# BrewPi_Shield.net
KiCad netlist of a schematic drawn in EAGLE
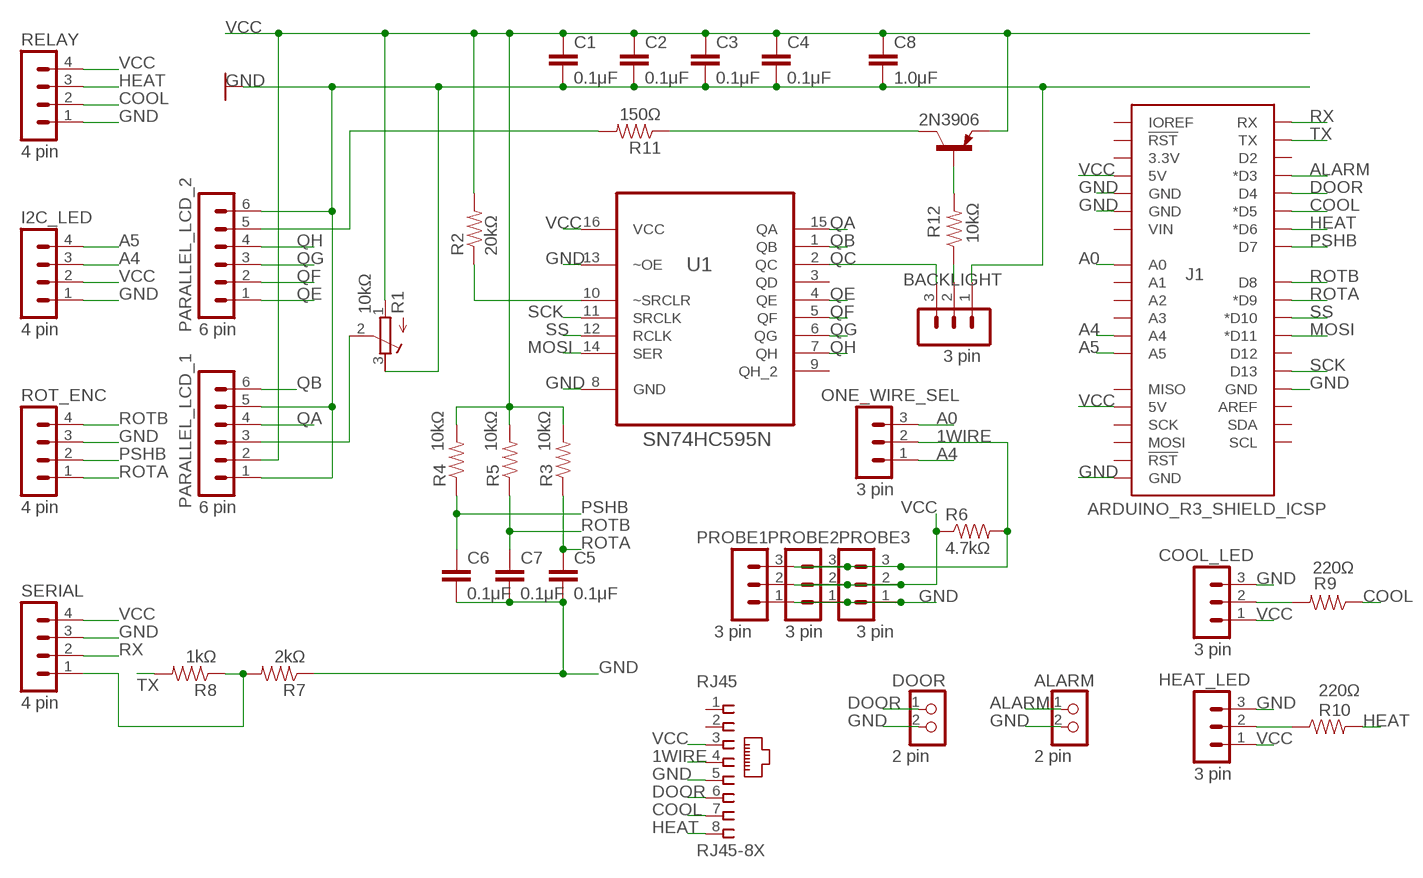
[diagram p0: schematic, sheet 1]

(export (version "E")
  (design (tool "Eeschema 10.0.6"))
  (components
    (comp (ref "ALARM")
      (value "2 pin")
      (footprint "eagle-import:HEADER02-1")
      (libsource (lib "eagle-import") (part "HEADER02-1"))
    )
    (comp (ref "BACKLIGHT")
      (value "3 pin")
      (footprint "eagle-import:HEADER03-1")
      (libsource (lib "eagle-import") (part "HEADER03-1"))
    )
    (comp (ref "C1")
      (value "0.1μF")
      (footprint "eagle-import:CAP-PTH-SMALL-KIT")
      (libsource (lib "eagle-import") (part "CAPKIT"))
    )
    (comp (ref "C2")
      (value "0.1μF")
      (footprint "eagle-import:CAP-PTH-SMALL-KIT")
      (libsource (lib "eagle-import") (part "CAPKIT"))
    )
    (comp (ref "C3")
      (value "0.1μF")
      (footprint "eagle-import:CAP-PTH-SMALL-KIT")
      (libsource (lib "eagle-import") (part "CAPKIT"))
    )
    (comp (ref "C4")
      (value "0.1μF")
      (footprint "eagle-import:CAP-PTH-SMALL-KIT")
      (libsource (lib "eagle-import") (part "CAPKIT"))
    )
    (comp (ref "C5")
      (value "0.1μF")
      (footprint "eagle-import:CAP-PTH-SMALL-KIT")
      (libsource (lib "eagle-import") (part "CAPKIT"))
    )
    (comp (ref "C6")
      (value "0.1μF")
      (footprint "eagle-import:CAP-PTH-SMALL-KIT")
      (libsource (lib "eagle-import") (part "CAPKIT"))
    )
    (comp (ref "C7")
      (value "0.1μF")
      (footprint "eagle-import:CAP-PTH-SMALL-KIT")
      (libsource (lib "eagle-import") (part "CAPKIT"))
    )
    (comp (ref "C8")
      (value "1.0μF")
      (footprint "eagle-import:CAP-PTH-SMALL-KIT")
      (libsource (lib "eagle-import") (part "CAPKIT"))
    )
    (comp (ref "COOL_LED")
      (value "3 pin")
      (footprint "eagle-import:HEADER03-1")
      (libsource (lib "eagle-import") (part "HEADER03-1"))
    )
    (comp (ref "DOOR")
      (value "2 pin")
      (footprint "eagle-import:HEADER02-1")
      (libsource (lib "eagle-import") (part "HEADER02-1"))
    )
    (comp (ref "HEAT_LED")
      (value "3 pin")
      (footprint "eagle-import:HEADER03-1")
      (libsource (lib "eagle-import") (part "HEADER03-1"))
    )
    (comp (ref "I2C_LED")
      (value "4 pin")
      (footprint "eagle-import:HEADER04-1")
      (libsource (lib "eagle-import") (part "HEADER04-1"))
    )
    (comp (ref "J1")
      (value "ARDUINO_R3_SHIELD_ICSP")
      (footprint "eagle-import:UNO_R3_SHIELD_ICSP")
      (libsource (lib "eagle-import") (part "ARDUINO_R3_SHIELD_ICSP"))
    )
    (comp (ref "ONE_WIRE_SEL")
      (value "3 pin")
      (footprint "eagle-import:HEADER03-1")
      (libsource (lib "eagle-import") (part "HEADER03-1"))
    )
    (comp (ref "PARALLEL_LCD_1")
      (value "6 pin")
      (footprint "eagle-import:HEADER06-1")
      (libsource (lib "eagle-import") (part "HEADER06-1"))
    )
    (comp (ref "PARALLEL_LCD_2")
      (value "6 pin")
      (footprint "eagle-import:HEADER06-1")
      (libsource (lib "eagle-import") (part "HEADER06-1"))
    )
    (comp (ref "PROBE1")
      (value "3 pin")
      (footprint "eagle-import:HEADER03-1")
      (libsource (lib "eagle-import") (part "HEADER03-1"))
    )
    (comp (ref "PROBE2")
      (value "3 pin")
      (footprint "eagle-import:HEADER03-1")
      (libsource (lib "eagle-import") (part "HEADER03-1"))
    )
    (comp (ref "PROBE3")
      (value "3 pin")
      (footprint "eagle-import:HEADER03-1")
      (libsource (lib "eagle-import") (part "HEADER03-1"))
    )
    (comp (ref "Q1")
      (value "2N3906")
      (footprint "eagle-import:TO92")
      (libsource (lib "eagle-import") (part "2N3906"))
    )
    (comp (ref "R1")
      (value "10kΩ")
      (footprint "eagle-import:RTRIM3296Y")
      (libsource (lib "eagle-import") (part "R-TRIMM3296Y"))
    )
    (comp (ref "R2")
      (value "20kΩ")
      (footprint "eagle-import:AXIAL-0.3")
      (libsource (lib "eagle-import") (part "RESISTORAXIAL-0.3"))
    )
    (comp (ref "R3")
      (value "10kΩ")
      (footprint "eagle-import:AXIAL-0.3")
      (libsource (lib "eagle-import") (part "RESISTORAXIAL-0.3"))
    )
    (comp (ref "R4")
      (value "10kΩ")
      (footprint "eagle-import:AXIAL-0.3")
      (libsource (lib "eagle-import") (part "RESISTORAXIAL-0.3"))
    )
    (comp (ref "R5")
      (value "10kΩ")
      (footprint "eagle-import:AXIAL-0.3")
      (libsource (lib "eagle-import") (part "RESISTORAXIAL-0.3"))
    )
    (comp (ref "R6")
      (value "4.7kΩ")
      (footprint "eagle-import:AXIAL-0.3")
      (libsource (lib "eagle-import") (part "RESISTORAXIAL-0.3"))
    )
    (comp (ref "R7")
      (value "2kΩ")
      (footprint "eagle-import:AXIAL-0.3")
      (libsource (lib "eagle-import") (part "RESISTORAXIAL-0.3"))
    )
    (comp (ref "R8")
      (value "1kΩ")
      (footprint "eagle-import:AXIAL-0.3")
      (libsource (lib "eagle-import") (part "RESISTORAXIAL-0.3"))
    )
    (comp (ref "R9")
      (value "220Ω")
      (footprint "eagle-import:AXIAL-0.3")
      (libsource (lib "eagle-import") (part "RESISTORAXIAL-0.3"))
    )
    (comp (ref "R10")
      (value "220Ω")
      (footprint "eagle-import:AXIAL-0.3")
      (libsource (lib "eagle-import") (part "RESISTORAXIAL-0.3"))
    )
    (comp (ref "R11")
      (value "150Ω")
      (footprint "eagle-import:AXIAL-0.3")
      (libsource (lib "eagle-import") (part "RESISTORAXIAL-0.3"))
    )
    (comp (ref "R12")
      (value "10kΩ")
      (footprint "eagle-import:AXIAL-0.3")
      (libsource (lib "eagle-import") (part "RESISTORAXIAL-0.3"))
    )
    (comp (ref "RELAY")
      (value "4 pin")
      (footprint "eagle-import:HEADER04-1")
      (libsource (lib "eagle-import") (part "HEADER04-1"))
    )
    (comp (ref "RJ45")
      (value "RJ45-8X")
      (footprint "eagle-import:RJ45-NO-SHIELD")
      (libsource (lib "eagle-import") (part "RJ45-8X"))
    )
    (comp (ref "ROT_ENC")
      (value "4 pin")
      (footprint "eagle-import:HEADER04-1")
      (libsource (lib "eagle-import") (part "HEADER04-1"))
    )
    (comp (ref "SERIAL")
      (value "4 pin")
      (footprint "eagle-import:HEADER04-1")
      (libsource (lib "eagle-import") (part "HEADER04-1"))
    )
    (comp (ref "U1")
      (value "SN74HC595N")
      (footprint "eagle-import:DIP254P762X508-16")
      (libsource (lib "eagle-import") (part "SN74HC595N"))
    )
  )
  (nets
    (net (code "1") (name "/1WIRE") (class "Default")
      (node (ref "ONE_WIRE_SEL") (pin "2") (pinfunction "2_2") (pintype "passive"))
      (node (ref "PROBE1") (pin "3") (pinfunction "3_3") (pintype "passive"))
      (node (ref "PROBE2") (pin "3") (pinfunction "3_3") (pintype "passive"))
      (node (ref "PROBE3") (pin "3") (pinfunction "3_3") (pintype "passive"))
      (node (ref "R6") (pin "P$2") (pinfunction "2_P$2") (pintype "passive"))
      (node (ref "RJ45") (pin "4") (pinfunction "4_4") (pintype "passive"))
    )
    (net (code "2") (name "/A0") (class "Default")
      (node (ref "J1") (pin "A0") (pinfunction "A0_A0") (pintype "bidirectional"))
      (node (ref "ONE_WIRE_SEL") (pin "3") (pinfunction "3_3") (pintype "passive"))
    )
    (net (code "3") (name "/A4") (class "Default")
      (node (ref "I2C_LED") (pin "3") (pinfunction "3_3") (pintype "passive"))
      (node (ref "J1") (pin "A4") (pinfunction "A4_A4") (pintype "bidirectional"))
      (node (ref "ONE_WIRE_SEL") (pin "1") (pinfunction "1_1") (pintype "passive"))
    )
    (net (code "4") (name "/A5") (class "Default")
      (node (ref "I2C_LED") (pin "4") (pinfunction "4_4") (pintype "passive"))
      (node (ref "J1") (pin "A5") (pinfunction "A5_A5") (pintype "bidirectional"))
    )
    (net (code "5") (name "/ALARM") (class "Default")
      (node (ref "ALARM") (pin "1") (pinfunction "1_1") (pintype "passive"))
      (node (ref "J1") (pin "D3") (pinfunction "*D3_D3") (pintype "bidirectional"))
    )
    (net (code "6") (name "/COOL") (class "Default")
      (node (ref "J1") (pin "D5") (pinfunction "*D5_D5") (pintype "bidirectional"))
      (node (ref "R9") (pin "P$1") (pinfunction "1_P$1") (pintype "passive"))
      (node (ref "RELAY") (pin "2") (pinfunction "2_2") (pintype "passive"))
      (node (ref "RJ45") (pin "7") (pinfunction "7_7") (pintype "passive"))
    )
    (net (code "7") (name "/DOOR") (class "Default")
      (node (ref "DOOR") (pin "1") (pinfunction "1_1") (pintype "passive"))
      (node (ref "J1") (pin "D4") (pinfunction "D4_D4") (pintype "bidirectional"))
      (node (ref "RJ45") (pin "6") (pinfunction "6_6") (pintype "passive"))
    )
    (net (code "8") (name "/HEAT") (class "Default")
      (node (ref "J1") (pin "D6") (pinfunction "*D6_D6") (pintype "bidirectional"))
      (node (ref "R10") (pin "P$2") (pinfunction "2_P$2") (pintype "passive"))
      (node (ref "RELAY") (pin "3") (pinfunction "3_3") (pintype "passive"))
      (node (ref "RJ45") (pin "8") (pinfunction "8_8") (pintype "passive"))
    )
    (net (code "9") (name "/MOSI") (class "Default")
      (node (ref "J1") (pin "D11") (pinfunction "*D11_D11") (pintype "bidirectional"))
      (node (ref "U1") (pin "14") (pinfunction "SER_14") (pintype "input"))
    )
    (net (code "10") (name "/PSHB") (class "Default")
      (node (ref "C6") (pin "1") (pinfunction "1_1") (pintype "passive"))
      (node (ref "J1") (pin "D7") (pinfunction "D7_D7") (pintype "bidirectional"))
      (node (ref "R4") (pin "P$1") (pinfunction "1_P$1") (pintype "passive"))
      (node (ref "ROT_ENC") (pin "2") (pinfunction "2_2") (pintype "passive"))
    )
    (net (code "11") (name "/QA") (class "Default")
      (node (ref "PARALLEL_LCD_1") (pin "4") (pinfunction "4_4") (pintype "passive"))
      (node (ref "U1") (pin "15") (pinfunction "QA_15") (pintype "output"))
    )
    (net (code "12") (name "/QB") (class "Default")
      (node (ref "PARALLEL_LCD_1") (pin "6") (pinfunction "6_6") (pintype "passive"))
      (node (ref "U1") (pin "1") (pinfunction "QB_1") (pintype "output"))
    )
    (net (code "13") (name "/QC") (class "Default")
      (node (ref "BACKLIGHT") (pin "3") (pinfunction "3_3") (pintype "passive"))
      (node (ref "U1") (pin "2") (pinfunction "QC_2") (pintype "output"))
    )
    (net (code "14") (name "/QE") (class "Default")
      (node (ref "PARALLEL_LCD_2") (pin "1") (pinfunction "1_1") (pintype "passive"))
      (node (ref "U1") (pin "4") (pinfunction "QE_4") (pintype "output"))
    )
    (net (code "15") (name "/QF") (class "Default")
      (node (ref "PARALLEL_LCD_2") (pin "2") (pinfunction "2_2") (pintype "passive"))
      (node (ref "U1") (pin "5") (pinfunction "QF_5") (pintype "output"))
    )
    (net (code "16") (name "/QG") (class "Default")
      (node (ref "PARALLEL_LCD_2") (pin "3") (pinfunction "3_3") (pintype "passive"))
      (node (ref "U1") (pin "6") (pinfunction "QG_6") (pintype "output"))
    )
    (net (code "17") (name "/QH") (class "Default")
      (node (ref "PARALLEL_LCD_2") (pin "4") (pinfunction "4_4") (pintype "passive"))
      (node (ref "U1") (pin "7") (pinfunction "QH_7") (pintype "output"))
    )
    (net (code "18") (name "/ROTA") (class "Default")
      (node (ref "C5") (pin "1") (pinfunction "1_1") (pintype "passive"))
      (node (ref "J1") (pin "D9") (pinfunction "*D9_D9") (pintype "bidirectional"))
      (node (ref "R3") (pin "P$1") (pinfunction "1_P$1") (pintype "passive"))
      (node (ref "ROT_ENC") (pin "1") (pinfunction "1_1") (pintype "passive"))
    )
    (net (code "19") (name "/ROTB") (class "Default")
      (node (ref "C7") (pin "1") (pinfunction "1_1") (pintype "passive"))
      (node (ref "J1") (pin "D8") (pinfunction "D8_D8") (pintype "bidirectional"))
      (node (ref "R5") (pin "P$1") (pinfunction "1_P$1") (pintype "passive"))
      (node (ref "ROT_ENC") (pin "4") (pinfunction "4_4") (pintype "passive"))
    )
    (net (code "20") (name "/RX") (class "Default")
      (node (ref "J1") (pin "RX") (pinfunction "RX_RX") (pintype "bidirectional"))
      (node (ref "SERIAL") (pin "2") (pinfunction "2_2") (pintype "passive"))
    )
    (net (code "21") (name "/SCK") (class "Default")
      (node (ref "J1") (pin "D13") (pinfunction "D13_D13") (pintype "bidirectional"))
      (node (ref "U1") (pin "11") (pinfunction "SRCLK_11") (pintype "input"))
    )
    (net (code "22") (name "/SS") (class "Default")
      (node (ref "J1") (pin "D10") (pinfunction "*D10_D10") (pintype "bidirectional"))
      (node (ref "U1") (pin "12") (pinfunction "RCLK_12") (pintype "input"))
    )
    (net (code "23") (name "/TX") (class "Default")
      (node (ref "J1") (pin "TX") (pinfunction "TX_TX") (pintype "bidirectional"))
      (node (ref "R8") (pin "P$2") (pinfunction "2_P$2") (pintype "passive"))
    )
    (net (code "24") (name "/VCC") (class "Default")
      (node (ref "C1") (pin "1") (pinfunction "1_1") (pintype "passive"))
      (node (ref "C2") (pin "1") (pinfunction "1_1") (pintype "passive"))
      (node (ref "C3") (pin "1") (pinfunction "1_1") (pintype "passive"))
      (node (ref "C4") (pin "1") (pinfunction "1_1") (pintype "passive"))
      (node (ref "C8") (pin "1") (pinfunction "1_1") (pintype "passive"))
      (node (ref "COOL_LED") (pin "1") (pinfunction "1_1") (pintype "passive"))
      (node (ref "HEAT_LED") (pin "1") (pinfunction "1_1") (pintype "passive"))
      (node (ref "I2C_LED") (pin "2") (pinfunction "2_2") (pintype "passive"))
      (node (ref "J1") (pin "5V") (pinfunction "5V_5V") (pintype "bidirectional"))
      (node (ref "J1") (pin "5V_ICSP") (pinfunction "5V_5V_ICSP") (pintype "bidirectional"))
      (node (ref "PARALLEL_LCD_1") (pin "2") (pinfunction "2_2") (pintype "passive"))
      (node (ref "PROBE1") (pin "2") (pinfunction "2_2") (pintype "passive"))
      (node (ref "PROBE2") (pin "2") (pinfunction "2_2") (pintype "passive"))
      (node (ref "PROBE3") (pin "2") (pinfunction "2_2") (pintype "passive"))
      (node (ref "Q1") (pin "3") (pinfunction "E_3") (pintype "passive"))
      (node (ref "R1") (pin "1") (pinfunction "A_1") (pintype "passive"))
      (node (ref "R2") (pin "P$2") (pinfunction "2_P$2") (pintype "passive"))
      (node (ref "R3") (pin "P$2") (pinfunction "2_P$2") (pintype "passive"))
      (node (ref "R4") (pin "P$2") (pinfunction "2_P$2") (pintype "passive"))
      (node (ref "R5") (pin "P$2") (pinfunction "2_P$2") (pintype "passive"))
      (node (ref "R6") (pin "P$1") (pinfunction "1_P$1") (pintype "passive"))
      (node (ref "RELAY") (pin "4") (pinfunction "4_4") (pintype "passive"))
      (node (ref "RJ45") (pin "3") (pinfunction "3_3") (pintype "passive"))
      (node (ref "SERIAL") (pin "4") (pinfunction "4_4") (pintype "passive"))
      (node (ref "U1") (pin "16") (pinfunction "VCC_16") (pintype "power_in"))
    )
    (net (code "25") (name "GND") (class "Default")
      (node (ref "ALARM") (pin "2") (pinfunction "2_2") (pintype "passive"))
      (node (ref "BACKLIGHT") (pin "1") (pinfunction "1_1") (pintype "passive"))
      (node (ref "C1") (pin "2") (pinfunction "2_2") (pintype "passive"))
      (node (ref "C2") (pin "2") (pinfunction "2_2") (pintype "passive"))
      (node (ref "C3") (pin "2") (pinfunction "2_2") (pintype "passive"))
      (node (ref "C4") (pin "2") (pinfunction "2_2") (pintype "passive"))
      (node (ref "C5") (pin "2") (pinfunction "2_2") (pintype "passive"))
      (node (ref "C6") (pin "2") (pinfunction "2_2") (pintype "passive"))
      (node (ref "C7") (pin "2") (pinfunction "2_2") (pintype "passive"))
      (node (ref "C8") (pin "2") (pinfunction "2_2") (pintype "passive"))
      (node (ref "COOL_LED") (pin "3") (pinfunction "3_3") (pintype "passive"))
      (node (ref "DOOR") (pin "2") (pinfunction "2_2") (pintype "passive"))
      (node (ref "HEAT_LED") (pin "3") (pinfunction "3_3") (pintype "passive"))
      (node (ref "I2C_LED") (pin "1") (pinfunction "1_1") (pintype "passive"))
      (node (ref "J1") (pin "GND@0") (pinfunction "GND_GND@0") (pintype "bidirectional"))
      (node (ref "J1") (pin "GND@1") (pinfunction "GND_GND@1") (pintype "bidirectional"))
      (node (ref "J1") (pin "GND@2") (pinfunction "GND_GND@2") (pintype "bidirectional"))
      (node (ref "J1") (pin "GND_ICSP") (pinfunction "GND_GND_ICSP") (pintype "bidirectional"))
      (node (ref "PARALLEL_LCD_1") (pin "1") (pinfunction "1_1") (pintype "passive"))
      (node (ref "PARALLEL_LCD_1") (pin "5") (pinfunction "5_5") (pintype "passive"))
      (node (ref "PARALLEL_LCD_2") (pin "6") (pinfunction "6_6") (pintype "passive"))
      (node (ref "PROBE1") (pin "1") (pinfunction "1_1") (pintype "passive"))
      (node (ref "PROBE2") (pin "1") (pinfunction "1_1") (pintype "passive"))
      (node (ref "PROBE3") (pin "1") (pinfunction "1_1") (pintype "passive"))
      (node (ref "R1") (pin "3") (pinfunction "E_3") (pintype "passive"))
      (node (ref "R7") (pin "P$1") (pinfunction "1_P$1") (pintype "passive"))
      (node (ref "RELAY") (pin "1") (pinfunction "1_1") (pintype "passive"))
      (node (ref "RJ45") (pin "5") (pinfunction "5_5") (pintype "passive"))
      (node (ref "ROT_ENC") (pin "3") (pinfunction "3_3") (pintype "passive"))
      (node (ref "SERIAL") (pin "3") (pinfunction "3_3") (pintype "passive"))
      (node (ref "U1") (pin "13") (pinfunction "~{OE}_13") (pintype "input"))
      (node (ref "U1") (pin "8") (pinfunction "GND_8") (pintype "passive"))
    )
    (net (code "26") (name "Net-(Q1-B)") (class "Default")
      (node (ref "Q1") (pin "2") (pinfunction "B_2") (pintype "passive"))
      (node (ref "R12") (pin "P$2") (pinfunction "2_P$2") (pintype "passive"))
    )
    (net (code "27") (name "Net-(Q1-C)") (class "Default")
      (node (ref "Q1") (pin "1") (pinfunction "C_1") (pintype "passive"))
      (node (ref "R11") (pin "P$1") (pinfunction "1_P$1") (pintype "passive"))
    )
    (net (code "28") (name "Net-(R1-S)") (class "Default")
      (node (ref "PARALLEL_LCD_1") (pin "3") (pinfunction "3_3") (pintype "passive"))
      (node (ref "R1") (pin "2") (pinfunction "S_2") (pintype "passive"))
    )
    (net (code "29") (name "Net-(R2-1)") (class "Default")
      (node (ref "R2") (pin "P$1") (pinfunction "1_P$1") (pintype "passive"))
      (node (ref "U1") (pin "10") (pinfunction "~{SRCLR}_10") (pintype "input"))
    )
    (net (code "30") (name "Net-(R7-2)") (class "Default")
      (node (ref "R7") (pin "P$2") (pinfunction "2_P$2") (pintype "passive"))
      (node (ref "R8") (pin "P$1") (pinfunction "1_P$1") (pintype "passive"))
      (node (ref "SERIAL") (pin "1") (pinfunction "1_1") (pintype "passive"))
    )
    (net (code "31") (name "Net-(R9-2)") (class "Default")
      (node (ref "COOL_LED") (pin "2") (pinfunction "2_2") (pintype "passive"))
      (node (ref "R9") (pin "P$2") (pinfunction "2_P$2") (pintype "passive"))
    )
    (net (code "32") (name "Net-(R10-1)") (class "Default")
      (node (ref "HEAT_LED") (pin "2") (pinfunction "2_2") (pintype "passive"))
      (node (ref "R10") (pin "P$1") (pinfunction "1_P$1") (pintype "passive"))
    )
    (net (code "33") (name "Net-(R11-2)") (class "Default")
      (node (ref "PARALLEL_LCD_2") (pin "5") (pinfunction "5_5") (pintype "passive"))
      (node (ref "R11") (pin "P$2") (pinfunction "2_P$2") (pintype "passive"))
    )
    (net (code "34") (name "Net-(R12-1)") (class "Default")
      (node (ref "BACKLIGHT") (pin "2") (pinfunction "2_2") (pintype "passive"))
      (node (ref "R12") (pin "P$1") (pinfunction "1_P$1") (pintype "passive"))
    )
    (net (code "35") (name "unconnected-(J1-Pad3.3V)") (class "Default")
      (node (ref "J1") (pin "3.3V") (pinfunction "3.3V_3.3V") (pintype "bidirectional"))
    )
    (net (code "36") (name "unconnected-(J1-PadA1)") (class "Default")
      (node (ref "J1") (pin "A1") (pinfunction "A1_A1") (pintype "bidirectional"))
    )
    (net (code "37") (name "unconnected-(J1-PadA2)") (class "Default")
      (node (ref "J1") (pin "A2") (pinfunction "A2_A2") (pintype "bidirectional"))
    )
    (net (code "38") (name "unconnected-(J1-PadA3)") (class "Default")
      (node (ref "J1") (pin "A3") (pinfunction "A3_A3") (pintype "bidirectional"))
    )
    (net (code "39") (name "unconnected-(J1-PadAREF)") (class "Default")
      (node (ref "J1") (pin "AREF") (pinfunction "AREF_AREF") (pintype "bidirectional"))
    )
    (net (code "40") (name "unconnected-(J1-PadD2)") (class "Default")
      (node (ref "J1") (pin "D2") (pinfunction "D2_D2") (pintype "bidirectional"))
    )
    (net (code "41") (name "unconnected-(J1-PadD12)") (class "Default")
      (node (ref "J1") (pin "D12") (pinfunction "D12_D12") (pintype "bidirectional"))
    )
    (net (code "42") (name "unconnected-(J1-PadIOREF)") (class "Default")
      (node (ref "J1") (pin "IOREF") (pinfunction "IOREF_IOREF") (pintype "bidirectional"))
    )
    (net (code "43") (name "unconnected-(J1-PadMISO)") (class "Default")
      (node (ref "J1") (pin "MISO") (pinfunction "MISO_MISO") (pintype "bidirectional"))
    )
    (net (code "44") (name "unconnected-(J1-PadMOSI)") (class "Default")
      (node (ref "J1") (pin "MOSI") (pinfunction "MOSI_MOSI") (pintype "bidirectional"))
    )
    (net (code "45") (name "unconnected-(J1-PadSCK)") (class "Default")
      (node (ref "J1") (pin "SCK") (pinfunction "SCK_SCK") (pintype "bidirectional"))
    )
    (net (code "46") (name "unconnected-(J1-PadSCL)") (class "Default")
      (node (ref "J1") (pin "SCL") (pinfunction "SCL_SCL") (pintype "bidirectional"))
    )
    (net (code "47") (name "unconnected-(J1-PadSDA)") (class "Default")
      (node (ref "J1") (pin "SDA") (pinfunction "SDA_SDA") (pintype "bidirectional"))
    )
    (net (code "48") (name "unconnected-(J1-PadVIN)") (class "Default")
      (node (ref "J1") (pin "VIN") (pinfunction "VIN_VIN") (pintype "bidirectional"))
    )
    (net (code "49") (name "unconnected-(J1-~{RST}-PadRES)") (class "Default")
      (node (ref "J1") (pin "RES") (pinfunction "~{RST}_RES") (pintype "bidirectional"))
    )
    (net (code "50") (name "unconnected-(J1-~{RST}-PadRST_ICSP)") (class "Default")
      (node (ref "J1") (pin "RST_ICSP") (pinfunction "~{RST}_RST_ICSP") (pintype "bidirectional"))
    )
    (net (code "51") (name "unconnected-(RJ45-Pad1)") (class "Default")
      (node (ref "RJ45") (pin "1") (pinfunction "1_1") (pintype "passive"))
    )
    (net (code "52") (name "unconnected-(RJ45-Pad2)") (class "Default")
      (node (ref "RJ45") (pin "2") (pinfunction "2_2") (pintype "passive"))
    )
    (net (code "53") (name "unconnected-(U1-QD-Pad3)") (class "Default")
      (node (ref "U1") (pin "3") (pinfunction "QD_3") (pintype "output"))
    )
    (net (code "54") (name "unconnected-(U1-QH_2-Pad9)") (class "Default")
      (node (ref "U1") (pin "9") (pinfunction "QH_2_9") (pintype "output"))
    )
  )
)
